# ice_header_adapter_pcb.net
KiCad netlist of a schematic drawn in EAGLE
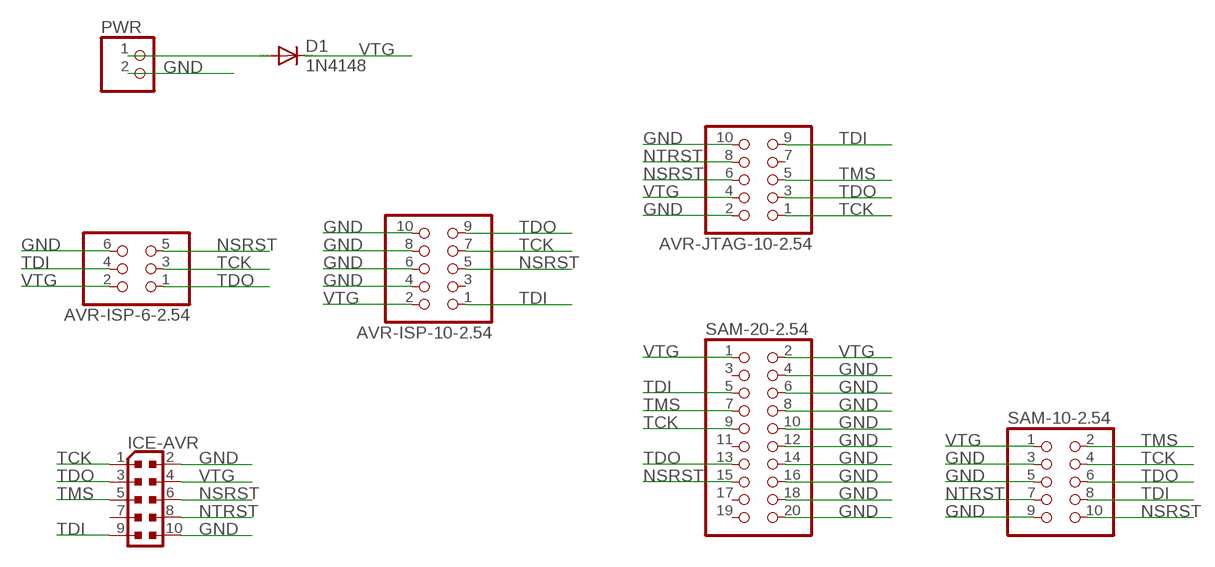
[diagram p0: schematic, sheet 1]

(export (version "E")
  (design (tool "Eeschema 10.0.6"))
  (components
    (comp (ref "AVR-ISP-6-2.54")
      (value "PINHD-2X3")
      (footprint "eagle-import:2X03")
      (libsource (lib "eagle-import") (part "PINHD-2X3"))
    )
    (comp (ref "AVR-ISP-10-2.54")
      (value "PINHD-2X5")
      (footprint "eagle-import:2X05")
      (libsource (lib "eagle-import") (part "PINHD-2X5"))
    )
    (comp (ref "AVR-JTAG-10-2.54")
      (value "PINHD-2X5")
      (footprint "eagle-import:2X05")
      (libsource (lib "eagle-import") (part "PINHD-2X5"))
    )
    (comp (ref "D1")
      (value "1N4148")
      (footprint "eagle-import:DO35-7")
      (libsource (lib "eagle-import") (part "1N4148DO35-7"))
    )
    (comp (ref "ICE-AVR")
      (value "PINHEAD_PINHD-2X5PASSO127")
      (footprint "eagle-import:PINHEAD_2X05_127")
      (libsource (lib "eagle-import") (part "PINHEAD_PINHD-2X5PASSO127"))
    )
    (comp (ref "PWR")
      (value "PINHD-1X2/90")
      (footprint "eagle-import:1X02_90")
      (libsource (lib "eagle-import") (part "PINHD-1X2/90"))
    )
    (comp (ref "SAM-10-2.54")
      (value "PINHD-2X5")
      (footprint "eagle-import:2X05")
      (libsource (lib "eagle-import") (part "PINHD-2X5"))
    )
    (comp (ref "SAM-20-2.54")
      (value "PINHD-2X10")
      (footprint "eagle-import:2X10")
      (libsource (lib "eagle-import") (part "PINHD-2X10"))
    )
  )
  (nets
    (net (code "1") (name "/GND") (class "Default")
      (node (ref "AVR-ISP-10-2.54") (pin "10") (pinfunction "10_10") (pintype "passive"))
      (node (ref "AVR-ISP-10-2.54") (pin "4") (pinfunction "4_4") (pintype "passive"))
      (node (ref "AVR-ISP-10-2.54") (pin "6") (pinfunction "6_6") (pintype "passive"))
      (node (ref "AVR-ISP-10-2.54") (pin "8") (pinfunction "8_8") (pintype "passive"))
      (node (ref "AVR-ISP-6-2.54") (pin "6") (pinfunction "6_6") (pintype "passive"))
      (node (ref "AVR-JTAG-10-2.54") (pin "10") (pinfunction "10_10") (pintype "passive"))
      (node (ref "AVR-JTAG-10-2.54") (pin "2") (pinfunction "2_2") (pintype "passive"))
      (node (ref "ICE-AVR") (pin "10") (pinfunction "10_10") (pintype "passive"))
      (node (ref "ICE-AVR") (pin "2") (pinfunction "2_2") (pintype "passive"))
      (node (ref "PWR") (pin "2") (pinfunction "2_2") (pintype "passive"))
      (node (ref "SAM-10-2.54") (pin "3") (pinfunction "3_3") (pintype "passive"))
      (node (ref "SAM-10-2.54") (pin "5") (pinfunction "5_5") (pintype "passive"))
      (node (ref "SAM-10-2.54") (pin "9") (pinfunction "9_9") (pintype "passive"))
      (node (ref "SAM-20-2.54") (pin "10") (pinfunction "10_10") (pintype "passive"))
      (node (ref "SAM-20-2.54") (pin "12") (pinfunction "12_12") (pintype "passive"))
      (node (ref "SAM-20-2.54") (pin "14") (pinfunction "14_14") (pintype "passive"))
      (node (ref "SAM-20-2.54") (pin "16") (pinfunction "16_16") (pintype "passive"))
      (node (ref "SAM-20-2.54") (pin "18") (pinfunction "18_18") (pintype "passive"))
      (node (ref "SAM-20-2.54") (pin "20") (pinfunction "20_20") (pintype "passive"))
      (node (ref "SAM-20-2.54") (pin "4") (pinfunction "4_4") (pintype "passive"))
      (node (ref "SAM-20-2.54") (pin "6") (pinfunction "6_6") (pintype "passive"))
      (node (ref "SAM-20-2.54") (pin "8") (pinfunction "8_8") (pintype "passive"))
    )
    (net (code "2") (name "/NSRST") (class "Default")
      (node (ref "AVR-ISP-10-2.54") (pin "5") (pinfunction "5_5") (pintype "passive"))
      (node (ref "AVR-ISP-6-2.54") (pin "5") (pinfunction "5_5") (pintype "passive"))
      (node (ref "AVR-JTAG-10-2.54") (pin "6") (pinfunction "6_6") (pintype "passive"))
      (node (ref "ICE-AVR") (pin "6") (pinfunction "6_6") (pintype "passive"))
      (node (ref "SAM-10-2.54") (pin "10") (pinfunction "10_10") (pintype "passive"))
      (node (ref "SAM-20-2.54") (pin "15") (pinfunction "15_15") (pintype "passive"))
    )
    (net (code "3") (name "/NTRST") (class "Default")
      (node (ref "AVR-JTAG-10-2.54") (pin "8") (pinfunction "8_8") (pintype "passive"))
      (node (ref "ICE-AVR") (pin "8") (pinfunction "8_8") (pintype "passive"))
      (node (ref "SAM-10-2.54") (pin "7") (pinfunction "7_7") (pintype "passive"))
    )
    (net (code "4") (name "/TCK") (class "Default")
      (node (ref "AVR-ISP-10-2.54") (pin "7") (pinfunction "7_7") (pintype "passive"))
      (node (ref "AVR-ISP-6-2.54") (pin "3") (pinfunction "3_3") (pintype "passive"))
      (node (ref "AVR-JTAG-10-2.54") (pin "1") (pinfunction "1_1") (pintype "passive"))
      (node (ref "ICE-AVR") (pin "1") (pinfunction "1_1") (pintype "passive"))
      (node (ref "SAM-10-2.54") (pin "4") (pinfunction "4_4") (pintype "passive"))
      (node (ref "SAM-20-2.54") (pin "9") (pinfunction "9_9") (pintype "passive"))
    )
    (net (code "5") (name "/TDI") (class "Default")
      (node (ref "AVR-ISP-10-2.54") (pin "1") (pinfunction "1_1") (pintype "passive"))
      (node (ref "AVR-ISP-6-2.54") (pin "4") (pinfunction "4_4") (pintype "passive"))
      (node (ref "AVR-JTAG-10-2.54") (pin "9") (pinfunction "9_9") (pintype "passive"))
      (node (ref "ICE-AVR") (pin "9") (pinfunction "9_9") (pintype "passive"))
      (node (ref "SAM-10-2.54") (pin "8") (pinfunction "8_8") (pintype "passive"))
      (node (ref "SAM-20-2.54") (pin "5") (pinfunction "5_5") (pintype "passive"))
    )
    (net (code "6") (name "/TDO") (class "Default")
      (node (ref "AVR-ISP-10-2.54") (pin "9") (pinfunction "9_9") (pintype "passive"))
      (node (ref "AVR-ISP-6-2.54") (pin "1") (pinfunction "1_1") (pintype "passive"))
      (node (ref "AVR-JTAG-10-2.54") (pin "3") (pinfunction "3_3") (pintype "passive"))
      (node (ref "ICE-AVR") (pin "3") (pinfunction "3_3") (pintype "passive"))
      (node (ref "SAM-10-2.54") (pin "6") (pinfunction "6_6") (pintype "passive"))
      (node (ref "SAM-20-2.54") (pin "13") (pinfunction "13_13") (pintype "passive"))
    )
    (net (code "7") (name "/TMS") (class "Default")
      (node (ref "AVR-JTAG-10-2.54") (pin "5") (pinfunction "5_5") (pintype "passive"))
      (node (ref "ICE-AVR") (pin "5") (pinfunction "5_5") (pintype "passive"))
      (node (ref "SAM-10-2.54") (pin "2") (pinfunction "2_2") (pintype "passive"))
      (node (ref "SAM-20-2.54") (pin "7") (pinfunction "7_7") (pintype "passive"))
    )
    (net (code "8") (name "/VTG") (class "Default")
      (node (ref "AVR-ISP-10-2.54") (pin "2") (pinfunction "2_2") (pintype "passive"))
      (node (ref "AVR-ISP-6-2.54") (pin "2") (pinfunction "2_2") (pintype "passive"))
      (node (ref "AVR-JTAG-10-2.54") (pin "4") (pinfunction "4_4") (pintype "passive"))
      (node (ref "D1") (pin "C") (pinfunction "C_C") (pintype "passive"))
      (node (ref "ICE-AVR") (pin "4") (pinfunction "4_4") (pintype "passive"))
      (node (ref "SAM-10-2.54") (pin "1") (pinfunction "1_1") (pintype "passive"))
      (node (ref "SAM-20-2.54") (pin "1") (pinfunction "1_1") (pintype "passive"))
      (node (ref "SAM-20-2.54") (pin "2") (pinfunction "2_2") (pintype "passive"))
    )
    (net (code "9") (name "Net-(D1-PadA)") (class "Default")
      (node (ref "D1") (pin "A") (pinfunction "A_A") (pintype "passive"))
      (node (ref "PWR") (pin "1") (pinfunction "1_1") (pintype "passive"))
    )
    (net (code "10") (name "unconnected-(AVR-ISP-10-2.54-Pad3)") (class "Default")
      (node (ref "AVR-ISP-10-2.54") (pin "3") (pinfunction "3_3") (pintype "passive"))
    )
    (net (code "11") (name "unconnected-(AVR-JTAG-10-2.54-Pad7)") (class "Default")
      (node (ref "AVR-JTAG-10-2.54") (pin "7") (pinfunction "7_7") (pintype "passive"))
    )
    (net (code "12") (name "unconnected-(ICE-AVR-Pad7)") (class "Default")
      (node (ref "ICE-AVR") (pin "7") (pinfunction "7_7") (pintype "passive"))
    )
    (net (code "13") (name "unconnected-(SAM-20-2.54-Pad3)") (class "Default")
      (node (ref "SAM-20-2.54") (pin "3") (pinfunction "3_3") (pintype "passive"))
    )
    (net (code "14") (name "unconnected-(SAM-20-2.54-Pad11)") (class "Default")
      (node (ref "SAM-20-2.54") (pin "11") (pinfunction "11_11") (pintype "passive"))
    )
    (net (code "15") (name "unconnected-(SAM-20-2.54-Pad17)") (class "Default")
      (node (ref "SAM-20-2.54") (pin "17") (pinfunction "17_17") (pintype "passive"))
    )
    (net (code "16") (name "unconnected-(SAM-20-2.54-Pad19)") (class "Default")
      (node (ref "SAM-20-2.54") (pin "19") (pinfunction "19_19") (pintype "passive"))
    )
  )
)
